# air-quality.net
KiCad netlist of a schematic drawn in EAGLE
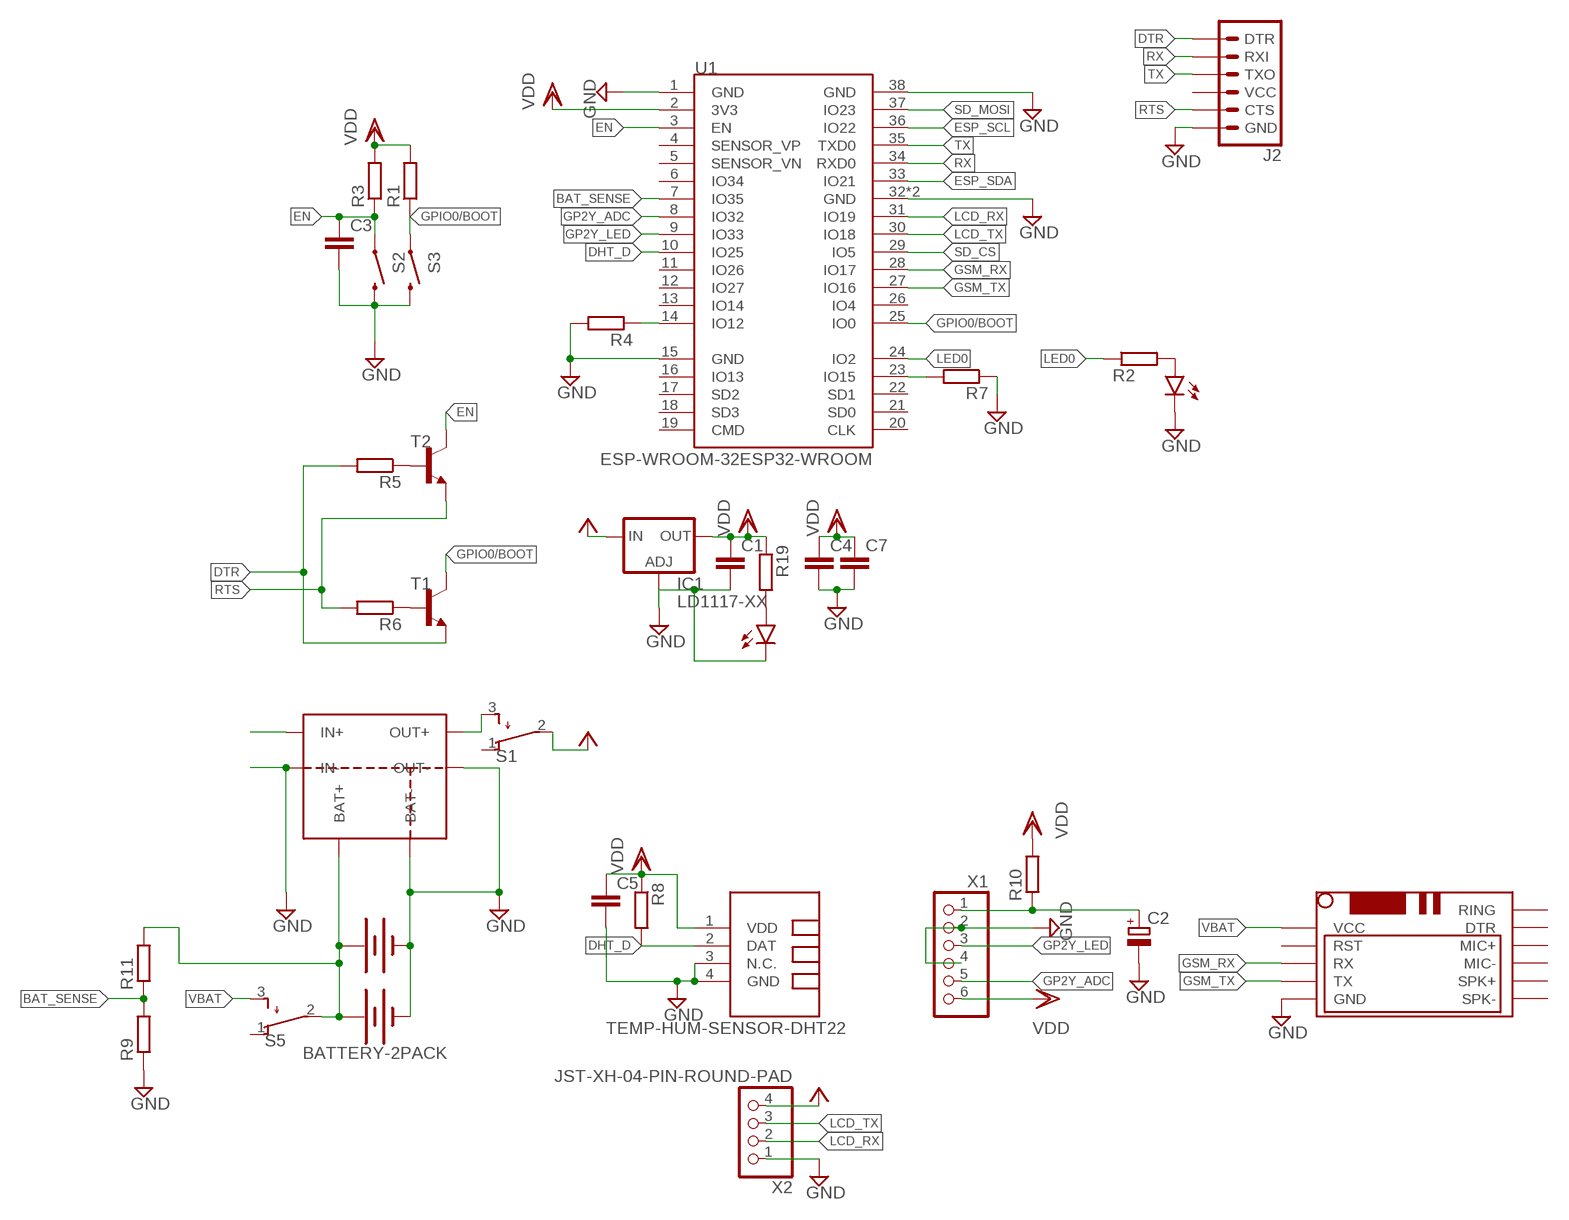
[diagram p0: schematic, sheet 1]

(export (version "E")
  (design (tool "Eeschema 10.0.6"))
  (components
    (comp (ref "C1")
      (value "C-EUC0805")
      (footprint "eagle-import:C0805")
      (libsource (lib "eagle-import") (part "C-EUC0805"))
    )
    (comp (ref "C2")
      (value "CPOL-EUE2.5-6")
      (footprint "eagle-import:E2,5-6")
      (libsource (lib "eagle-import") (part "CPOL-EUE2.5-6"))
    )
    (comp (ref "C3")
      (value "C-EUC0805")
      (footprint "eagle-import:C0805")
      (libsource (lib "eagle-import") (part "C-EUC0805"))
    )
    (comp (ref "C4")
      (value "C-EUC0805")
      (footprint "eagle-import:C0805")
      (libsource (lib "eagle-import") (part "C-EUC0805"))
    )
    (comp (ref "C5")
      (value "C-EUC0805")
      (footprint "eagle-import:C0805")
      (libsource (lib "eagle-import") (part "C-EUC0805"))
    )
    (comp (ref "C7")
      (value "C-EUC0805")
      (footprint "eagle-import:C0805")
      (libsource (lib "eagle-import") (part "C-EUC0805"))
    )
    (comp (ref "IC1")
      (value "LD1117-XX")
      (footprint "eagle-import:SOT230P700X180-4N")
      (libsource (lib "eagle-import") (part "LD1117-XX"))
    )
    (comp (ref "J2")
      (value "6_PIN_SERIAL_TARGETFEMALE")
      (footprint "eagle-import:6_PIN_SERIAL_TARGET_SIDE_W_SILK-FEMALE")
      (libsource (lib "eagle-import") (part "6_PIN_SERIAL_TARGETFEMALE"))
    )
    (comp (ref "LED12")
      (value "LEDCHIP-LED0805")
      (footprint "eagle-import:CHIP-LED0805")
      (libsource (lib "eagle-import") (part "LEDCHIP-LED0805"))
    )
    (comp (ref "POW")
      (value "LEDCHIP-LED0603")
      (footprint "eagle-import:CHIP-LED0603")
      (libsource (lib "eagle-import") (part "LEDCHIP-LED0603"))
    )
    (comp (ref "R1")
      (value "R-EU_R0805")
      (footprint "eagle-import:R0805")
      (libsource (lib "eagle-import") (part "R-EU_R0805"))
    )
    (comp (ref "R2")
      (value "R-EU_R0805")
      (footprint "eagle-import:R0805")
      (libsource (lib "eagle-import") (part "R-EU_R0805"))
    )
    (comp (ref "R3")
      (value "R-EU_R0805")
      (footprint "eagle-import:R0805")
      (libsource (lib "eagle-import") (part "R-EU_R0805"))
    )
    (comp (ref "R4")
      (value "R-EU_R0805")
      (footprint "eagle-import:R0805")
      (libsource (lib "eagle-import") (part "R-EU_R0805"))
    )
    (comp (ref "R5")
      (value "R-EU_R0805")
      (footprint "eagle-import:R0805")
      (libsource (lib "eagle-import") (part "R-EU_R0805"))
    )
    (comp (ref "R6")
      (value "R-EU_R0805")
      (footprint "eagle-import:R0805")
      (libsource (lib "eagle-import") (part "R-EU_R0805"))
    )
    (comp (ref "R7")
      (value "R-EU_R0805")
      (footprint "eagle-import:R0805")
      (libsource (lib "eagle-import") (part "R-EU_R0805"))
    )
    (comp (ref "R8")
      (value "R-EU_R0805")
      (footprint "eagle-import:R0805")
      (libsource (lib "eagle-import") (part "R-EU_R0805"))
    )
    (comp (ref "R9")
      (value "R-EU_R0805")
      (footprint "eagle-import:R0805")
      (libsource (lib "eagle-import") (part "R-EU_R0805"))
    )
    (comp (ref "R10")
      (value "R-EU_0204/7")
      (footprint "eagle-import:0204_7")
      (libsource (lib "eagle-import") (part "R-EU_0204/7"))
    )
    (comp (ref "R11")
      (value "R-EU_R0805")
      (footprint "eagle-import:R0805")
      (libsource (lib "eagle-import") (part "R-EU_R0805"))
    )
    (comp (ref "R19")
      (value "R-EU_R0805")
      (footprint "eagle-import:R0805")
      (libsource (lib "eagle-import") (part "R-EU_R0805"))
    )
    (comp (ref "S1")
      (value "TL32PO")
      (footprint "eagle-import:TL3XPO")
      (libsource (lib "eagle-import") (part "TL32PO"))
    )
    (comp (ref "S2")
      (value "ESP_BOOT")
      (footprint "eagle-import:TACTILE-SWITCH-1101NE")
      (libsource (lib "eagle-import") (part "SPST-SWSMD-1101NE"))
    )
    (comp (ref "S3")
      (value "ESP_EN")
      (footprint "eagle-import:TACTILE-SWITCH-1101NE")
      (libsource (lib "eagle-import") (part "SPST-SWSMD-1101NE"))
    )
    (comp (ref "S5")
      (value "TL32PO")
      (footprint "eagle-import:TL3XPO")
      (libsource (lib "eagle-import") (part "TL32PO"))
    )
    (comp (ref "T1")
      (value "BC808-NPN-SOT23-BEC")
      (footprint "eagle-import:SOT23-BEC")
      (libsource (lib "eagle-import") (part "-NPN-SOT23-BECBC808"))
    )
    (comp (ref "T2")
      (value "BC808-NPN-SOT23-BEC")
      (footprint "eagle-import:SOT23-BEC")
      (libsource (lib "eagle-import") (part "-NPN-SOT23-BECBC808"))
    )
    (comp (ref "U$1")
      (value "BMS-LITHIUM")
      (footprint "eagle-import:BMS-LITHIUM")
      (libsource (lib "eagle-import") (part "BMS-LITHIUM"))
    )
    (comp (ref "U$2")
      (value "BATTERY-2PACK")
      (footprint "eagle-import:BATTERY-18650-HOLDER-2PACK-SMD")
      (libsource (lib "eagle-import") (part "BATTERY-2PACK"))
    )
    (comp (ref "U$3")
      (value "TEMP-HUM-SENSOR-DHT22")
      (footprint "eagle-import:TEMP-HUM-SENSOR-DHT22")
      (libsource (lib "eagle-import") (part "TEMP-HUM-SENSOR-DHT22"))
    )
    (comp (ref "U$4")
      (value "SIM800LMODULE")
      (footprint "eagle-import:SIM800LMODULE")
      (libsource (lib "eagle-import") (part "SIM800LMODULE"))
    )
    (comp (ref "U1")
      (value "ESP-WROOM-32ESP32-WROOM")
      (footprint "eagle-import:ESP-WROOM-32")
      (libsource (lib "eagle-import") (part "ESP-WROOM-32ESP32-WROOM"))
    )
    (comp (ref "X1")
      (value "JST-XH-06-PIN-ROUND-PAD")
      (footprint "eagle-import:JST-XH-06-PACKAGE-ROUND-PAD")
      (libsource (lib "eagle-import") (part "JST-XH-06-PIN-ROUND-PAD"))
    )
    (comp (ref "X2")
      (value "JST-XH-04-PIN-ROUND-PAD")
      (footprint "eagle-import:JST-XH-04-PACKAGE-ROUND-PAD")
      (libsource (lib "eagle-import") (part "JST-XH-04-PIN-ROUND-PAD"))
    )
  )
  (nets
    (net (code "1") (name "BAT_SENSE") (class "Default")
      (node (ref "R11") (pin "1") (pinfunction "1_1") (pintype "passive"))
      (node (ref "R9") (pin "2") (pinfunction "2_2") (pintype "passive"))
      (node (ref "U1") (pin "7") (pinfunction "IO35_7") (pintype "bidirectional"))
    )
    (net (code "2") (name "DHT_D") (class "Default")
      (node (ref "R8") (pin "2") (pinfunction "2_2") (pintype "passive"))
      (node (ref "U$3") (pin "2") (pinfunction "DAT_2") (pintype "bidirectional"))
      (node (ref "U1") (pin "10") (pinfunction "IO25_10") (pintype "bidirectional"))
    )
    (net (code "3") (name "DTR") (class "Default")
      (node (ref "J2") (pin "1") (pinfunction "DTR_1") (pintype "passive"))
      (node (ref "R5") (pin "2") (pinfunction "2_2") (pintype "passive"))
      (node (ref "T1") (pin "E") (pinfunction "E_E") (pintype "passive"))
    )
    (net (code "4") (name "EN") (class "Default")
      (node (ref "C3") (pin "1") (pinfunction "1_1") (pintype "passive"))
      (node (ref "R3") (pin "1") (pinfunction "1_1") (pintype "passive"))
      (node (ref "S2") (pin "1") (pinfunction "1_1") (pintype "passive"))
      (node (ref "T2") (pin "C") (pinfunction "C_C") (pintype "passive"))
      (node (ref "U1") (pin "3") (pinfunction "EN_3") (pintype "input"))
    )
    (net (code "5") (name "ESP_SCL") (class "Default")
      (node (ref "U1") (pin "36") (pinfunction "IO22_36") (pintype "bidirectional"))
    )
    (net (code "6") (name "ESP_SDA") (class "Default")
      (node (ref "U1") (pin "33") (pinfunction "IO21_33") (pintype "bidirectional"))
    )
    (net (code "7") (name "GND") (class "Default")
      (node (ref "C1") (pin "2") (pinfunction "2_2") (pintype "passive"))
      (node (ref "C2") (pin "-") (pinfunction "-_-") (pintype "passive"))
      (node (ref "C3") (pin "2") (pinfunction "2_2") (pintype "passive"))
      (node (ref "C4") (pin "2") (pinfunction "2_2") (pintype "passive"))
      (node (ref "C5") (pin "2") (pinfunction "2_2") (pintype "passive"))
      (node (ref "C7") (pin "2") (pinfunction "2_2") (pintype "passive"))
      (node (ref "IC1") (pin "1") (pinfunction "ADJ_1") (pintype "input"))
      (node (ref "J2") (pin "6") (pinfunction "GND_6") (pintype "passive"))
      (node (ref "LED12") (pin "C") (pinfunction "C_C") (pintype "passive"))
      (node (ref "POW") (pin "C") (pinfunction "C_C") (pintype "passive"))
      (node (ref "R4") (pin "2") (pinfunction "2_2") (pintype "passive"))
      (node (ref "R7") (pin "1") (pinfunction "1_1") (pintype "passive"))
      (node (ref "R9") (pin "1") (pinfunction "1_1") (pintype "passive"))
      (node (ref "S2") (pin "2") (pinfunction "2_2") (pintype "passive"))
      (node (ref "S3") (pin "2") (pinfunction "2_2") (pintype "passive"))
      (node (ref "U$1") (pin "BAT-") (pinfunction "BAT-_BAT-") (pintype "output"))
      (node (ref "U$1") (pin "IN-") (pinfunction "IN-_IN-") (pintype "power_in"))
      (node (ref "U$1") (pin "OUT-") (pinfunction "OUT-_OUT-") (pintype "output"))
      (node (ref "U$2") (pin "-0") (pinfunction "-0_-0") (pintype "power_in"))
      (node (ref "U$2") (pin "-1") (pinfunction "-1_-1") (pintype "power_in"))
      (node (ref "U$3") (pin "3") (pinfunction "N.C._3") (pintype "passive"))
      (node (ref "U$3") (pin "4") (pinfunction "GND_4") (pintype "power_in"))
      (node (ref "U$4") (pin "GND") (pinfunction "GND_GND") (pintype "bidirectional"))
      (node (ref "U1") (pin "1") (pinfunction "GND_1") (pintype "power_in"))
      (node (ref "U1") (pin "15") (pinfunction "GND_15") (pintype "power_in"))
      (node (ref "U1") (pin "32") (pinfunction "GND_32") (pintype "power_in"))
      (node (ref "U1") (pin "38") (pinfunction "GND_38") (pintype "power_in"))
      (node (ref "U1") (pin "GND") (pinfunction "GND_GND") (pintype "power_in"))
      (node (ref "X1") (pin "2") (pinfunction "2_2") (pintype "passive"))
      (node (ref "X1") (pin "4") (pinfunction "4_4") (pintype "passive"))
      (node (ref "X2") (pin "1") (pinfunction "1_1") (pintype "passive"))
    )
    (net (code "8") (name "GP2Y_ADC") (class "Default")
      (node (ref "U1") (pin "8") (pinfunction "IO32_8") (pintype "bidirectional"))
      (node (ref "X1") (pin "5") (pinfunction "5_5") (pintype "passive"))
    )
    (net (code "9") (name "GP2Y_LED") (class "Default")
      (node (ref "U1") (pin "9") (pinfunction "IO33_9") (pintype "bidirectional"))
      (node (ref "X1") (pin "3") (pinfunction "3_3") (pintype "passive"))
    )
    (net (code "10") (name "GPIO0{slash}BOOT") (class "Default")
      (node (ref "R1") (pin "1") (pinfunction "1_1") (pintype "passive"))
      (node (ref "S3") (pin "1") (pinfunction "1_1") (pintype "passive"))
      (node (ref "T1") (pin "C") (pinfunction "C_C") (pintype "passive"))
      (node (ref "U1") (pin "25") (pinfunction "IO0_25") (pintype "bidirectional"))
    )
    (net (code "11") (name "GSM_RX") (class "Default")
      (node (ref "U$4") (pin "RX") (pinfunction "RX_RX") (pintype "bidirectional"))
      (node (ref "U1") (pin "28") (pinfunction "IO17_28") (pintype "bidirectional"))
    )
    (net (code "12") (name "GSM_TX") (class "Default")
      (node (ref "U$4") (pin "TX") (pinfunction "TX_TX") (pintype "bidirectional"))
      (node (ref "U1") (pin "27") (pinfunction "IO16_27") (pintype "bidirectional"))
    )
    (net (code "13") (name "LCD_RX") (class "Default")
      (node (ref "U1") (pin "31") (pinfunction "IO19_31") (pintype "bidirectional"))
      (node (ref "X2") (pin "2") (pinfunction "2_2") (pintype "passive"))
    )
    (net (code "14") (name "LCD_TX") (class "Default")
      (node (ref "U1") (pin "30") (pinfunction "IO18_30") (pintype "bidirectional"))
      (node (ref "X2") (pin "3") (pinfunction "3_3") (pintype "passive"))
    )
    (net (code "15") (name "LED0") (class "Default")
      (node (ref "R2") (pin "1") (pinfunction "1_1") (pintype "passive"))
      (node (ref "U1") (pin "24") (pinfunction "IO2_24") (pintype "bidirectional"))
    )
    (net (code "16") (name "Net-(C2-Pad+)") (class "Default")
      (node (ref "C2") (pin "+") (pinfunction "+_+") (pintype "passive"))
      (node (ref "R10") (pin "1") (pinfunction "1_1") (pintype "passive"))
      (node (ref "X1") (pin "1") (pinfunction "1_1") (pintype "passive"))
    )
    (net (code "17") (name "Net-(LED12-PadA)") (class "Default")
      (node (ref "LED12") (pin "A") (pinfunction "A_A") (pintype "passive"))
      (node (ref "R2") (pin "2") (pinfunction "2_2") (pintype "passive"))
    )
    (net (code "18") (name "Net-(POW-PadA)") (class "Default")
      (node (ref "POW") (pin "A") (pinfunction "A_A") (pintype "passive"))
      (node (ref "R19") (pin "2") (pinfunction "2_2") (pintype "passive"))
    )
    (net (code "19") (name "Net-(R5-Pad1)") (class "Default")
      (node (ref "R5") (pin "1") (pinfunction "1_1") (pintype "passive"))
      (node (ref "T2") (pin "B") (pinfunction "B_B") (pintype "passive"))
    )
    (net (code "20") (name "Net-(R6-Pad1)") (class "Default")
      (node (ref "R6") (pin "1") (pinfunction "1_1") (pintype "passive"))
      (node (ref "T1") (pin "B") (pinfunction "B_B") (pintype "passive"))
    )
    (net (code "21") (name "Net-(S1-S)") (class "Default")
      (node (ref "S1") (pin "3") (pinfunction "S_3") (pintype "passive"))
      (node (ref "U$1") (pin "OUT+") (pinfunction "OUT+_OUT+") (pintype "output"))
    )
    (net (code "22") (name "Net-(S5-P)") (class "Default")
      (node (ref "R11") (pin "2") (pinfunction "2_2") (pintype "passive"))
      (node (ref "S5") (pin "2") (pinfunction "P_2") (pintype "passive"))
      (node (ref "U$1") (pin "BAT+") (pinfunction "BAT+_BAT+") (pintype "output"))
      (node (ref "U$2") (pin "+0") (pinfunction "+0_+0") (pintype "power_in"))
      (node (ref "U$2") (pin "+1") (pinfunction "+1_+1") (pintype "power_in"))
    )
    (net (code "23") (name "Net-(U1-IO12)") (class "Default")
      (node (ref "R4") (pin "1") (pinfunction "1_1") (pintype "passive"))
      (node (ref "U1") (pin "14") (pinfunction "IO12_14") (pintype "bidirectional"))
    )
    (net (code "24") (name "Net-(U1-IO15)") (class "Default")
      (node (ref "R7") (pin "2") (pinfunction "2_2") (pintype "passive"))
      (node (ref "U1") (pin "23") (pinfunction "IO15_23") (pintype "bidirectional"))
    )
    (net (code "25") (name "RTS") (class "Default")
      (node (ref "J2") (pin "5") (pinfunction "CTS_5") (pintype "passive"))
      (node (ref "R6") (pin "2") (pinfunction "2_2") (pintype "passive"))
      (node (ref "T2") (pin "E") (pinfunction "E_E") (pintype "passive"))
    )
    (net (code "26") (name "RX") (class "Default")
      (node (ref "J2") (pin "3") (pinfunction "RXI_3") (pintype "passive"))
      (node (ref "U1") (pin "34") (pinfunction "RXD0_34") (pintype "bidirectional"))
    )
    (net (code "27") (name "SD_CS") (class "Default")
      (node (ref "U1") (pin "29") (pinfunction "IO5_29") (pintype "bidirectional"))
    )
    (net (code "28") (name "SD_MOSI") (class "Default")
      (node (ref "U1") (pin "37") (pinfunction "IO23_37") (pintype "bidirectional"))
    )
    (net (code "29") (name "TX") (class "Default")
      (node (ref "J2") (pin "2") (pinfunction "TXO_2") (pintype "passive"))
      (node (ref "U1") (pin "35") (pinfunction "TXD0_35") (pintype "bidirectional"))
    )
    (net (code "30") (name "VBAT") (class "Default")
      (node (ref "S5") (pin "3") (pinfunction "S_3") (pintype "passive"))
      (node (ref "U$4") (pin "VCC") (pinfunction "VCC_VCC") (pintype "bidirectional"))
    )
    (net (code "31") (name "VCC") (class "Default")
      (node (ref "IC1") (pin "3") (pinfunction "IN_3") (pintype "input"))
      (node (ref "S1") (pin "2") (pinfunction "P_2") (pintype "passive"))
      (node (ref "X2") (pin "4") (pinfunction "4_4") (pintype "passive"))
    )
    (net (code "32") (name "VDD") (class "Default")
      (node (ref "C1") (pin "1") (pinfunction "1_1") (pintype "passive"))
      (node (ref "C4") (pin "1") (pinfunction "1_1") (pintype "passive"))
      (node (ref "C5") (pin "1") (pinfunction "1_1") (pintype "passive"))
      (node (ref "C7") (pin "1") (pinfunction "1_1") (pintype "passive"))
      (node (ref "IC1") (pin "2") (pinfunction "OUT_2") (pintype "passive"))
      (node (ref "IC1") (pin "4") (pinfunction "OUT_4") (pintype "passive"))
      (node (ref "R1") (pin "2") (pinfunction "2_2") (pintype "passive"))
      (node (ref "R10") (pin "2") (pinfunction "2_2") (pintype "passive"))
      (node (ref "R19") (pin "1") (pinfunction "1_1") (pintype "passive"))
      (node (ref "R3") (pin "2") (pinfunction "2_2") (pintype "passive"))
      (node (ref "R8") (pin "1") (pinfunction "1_1") (pintype "passive"))
      (node (ref "U$3") (pin "1") (pinfunction "VDD_1") (pintype "power_in"))
      (node (ref "U1") (pin "2") (pinfunction "3V3_2") (pintype "power_in"))
      (node (ref "X1") (pin "6") (pinfunction "6_6") (pintype "passive"))
    )
    (net (code "33") (name "unconnected-(J2-VCC-Pad4)") (class "Default")
      (node (ref "J2") (pin "4") (pinfunction "VCC_4") (pintype "passive"))
    )
    (net (code "34") (name "unconnected-(S1-O-Pad1)") (class "Default")
      (node (ref "S1") (pin "1") (pinfunction "O_1") (pintype "passive"))
    )
    (net (code "35") (name "unconnected-(S5-O-Pad1)") (class "Default")
      (node (ref "S5") (pin "1") (pinfunction "O_1") (pintype "passive"))
    )
    (net (code "36") (name "unconnected-(U$1-PadIN+)") (class "Default")
      (node (ref "U$1") (pin "IN+") (pinfunction "IN+_IN+") (pintype "power_in"))
    )
    (net (code "37") (name "unconnected-(U$4-PadDTR)") (class "Default")
      (node (ref "U$4") (pin "DTR") (pinfunction "DTR_DTR") (pintype "bidirectional"))
    )
    (net (code "38") (name "unconnected-(U$4-PadMIC+)") (class "Default")
      (node (ref "U$4") (pin "MIC+") (pinfunction "MIC+_MIC+") (pintype "bidirectional"))
    )
    (net (code "39") (name "unconnected-(U$4-PadMIC-)") (class "Default")
      (node (ref "U$4") (pin "MIC-") (pinfunction "MIC-_MIC-") (pintype "bidirectional"))
    )
    (net (code "40") (name "unconnected-(U$4-PadRING)") (class "Default")
      (node (ref "U$4") (pin "RING") (pinfunction "RING_RING") (pintype "bidirectional"))
    )
    (net (code "41") (name "unconnected-(U$4-PadRST)") (class "Default")
      (node (ref "U$4") (pin "RST") (pinfunction "RST_RST") (pintype "bidirectional"))
    )
    (net (code "42") (name "unconnected-(U$4-PadSPK+)") (class "Default")
      (node (ref "U$4") (pin "SPK+") (pinfunction "SPK+_SPK+") (pintype "bidirectional"))
    )
    (net (code "43") (name "unconnected-(U$4-PadSPK-)") (class "Default")
      (node (ref "U$4") (pin "SPK-") (pinfunction "SPK-_SPK-") (pintype "bidirectional"))
    )
    (net (code "44") (name "unconnected-(U1-CLK-Pad20)") (class "Default")
      (node (ref "U1") (pin "20") (pinfunction "CLK_20") (pintype "bidirectional"))
    )
    (net (code "45") (name "unconnected-(U1-CMD-Pad19)") (class "Default")
      (node (ref "U1") (pin "19") (pinfunction "CMD_19") (pintype "bidirectional"))
    )
    (net (code "46") (name "unconnected-(U1-IO4-Pad26)") (class "Default")
      (node (ref "U1") (pin "26") (pinfunction "IO4_26") (pintype "bidirectional"))
    )
    (net (code "47") (name "unconnected-(U1-IO13-Pad16)") (class "Default")
      (node (ref "U1") (pin "16") (pinfunction "IO13_16") (pintype "bidirectional"))
    )
    (net (code "48") (name "unconnected-(U1-IO14-Pad13)") (class "Default")
      (node (ref "U1") (pin "13") (pinfunction "IO14_13") (pintype "bidirectional"))
    )
    (net (code "49") (name "unconnected-(U1-IO26-Pad11)") (class "Default")
      (node (ref "U1") (pin "11") (pinfunction "IO26_11") (pintype "bidirectional"))
    )
    (net (code "50") (name "unconnected-(U1-IO27-Pad12)") (class "Default")
      (node (ref "U1") (pin "12") (pinfunction "IO27_12") (pintype "bidirectional"))
    )
    (net (code "51") (name "unconnected-(U1-IO34-Pad6)") (class "Default")
      (node (ref "U1") (pin "6") (pinfunction "IO34_6") (pintype "bidirectional"))
    )
    (net (code "52") (name "unconnected-(U1-SD0-Pad21)") (class "Default")
      (node (ref "U1") (pin "21") (pinfunction "SD0_21") (pintype "bidirectional"))
    )
    (net (code "53") (name "unconnected-(U1-SD1-Pad22)") (class "Default")
      (node (ref "U1") (pin "22") (pinfunction "SD1_22") (pintype "bidirectional"))
    )
    (net (code "54") (name "unconnected-(U1-SD2-Pad17)") (class "Default")
      (node (ref "U1") (pin "17") (pinfunction "SD2_17") (pintype "bidirectional"))
    )
    (net (code "55") (name "unconnected-(U1-SD3-Pad18)") (class "Default")
      (node (ref "U1") (pin "18") (pinfunction "SD3_18") (pintype "bidirectional"))
    )
    (net (code "56") (name "unconnected-(U1-SENSOR_VN-Pad5)") (class "Default")
      (node (ref "U1") (pin "5") (pinfunction "SENSOR_VN_5") (pintype "bidirectional"))
    )
    (net (code "57") (name "unconnected-(U1-SENSOR_VP-Pad4)") (class "Default")
      (node (ref "U1") (pin "4") (pinfunction "SENSOR_VP_4") (pintype "bidirectional"))
    )
  )
)
